# RFM50_to_IWING-MRF_2.net
KiCad netlist of a schematic drawn in EAGLE
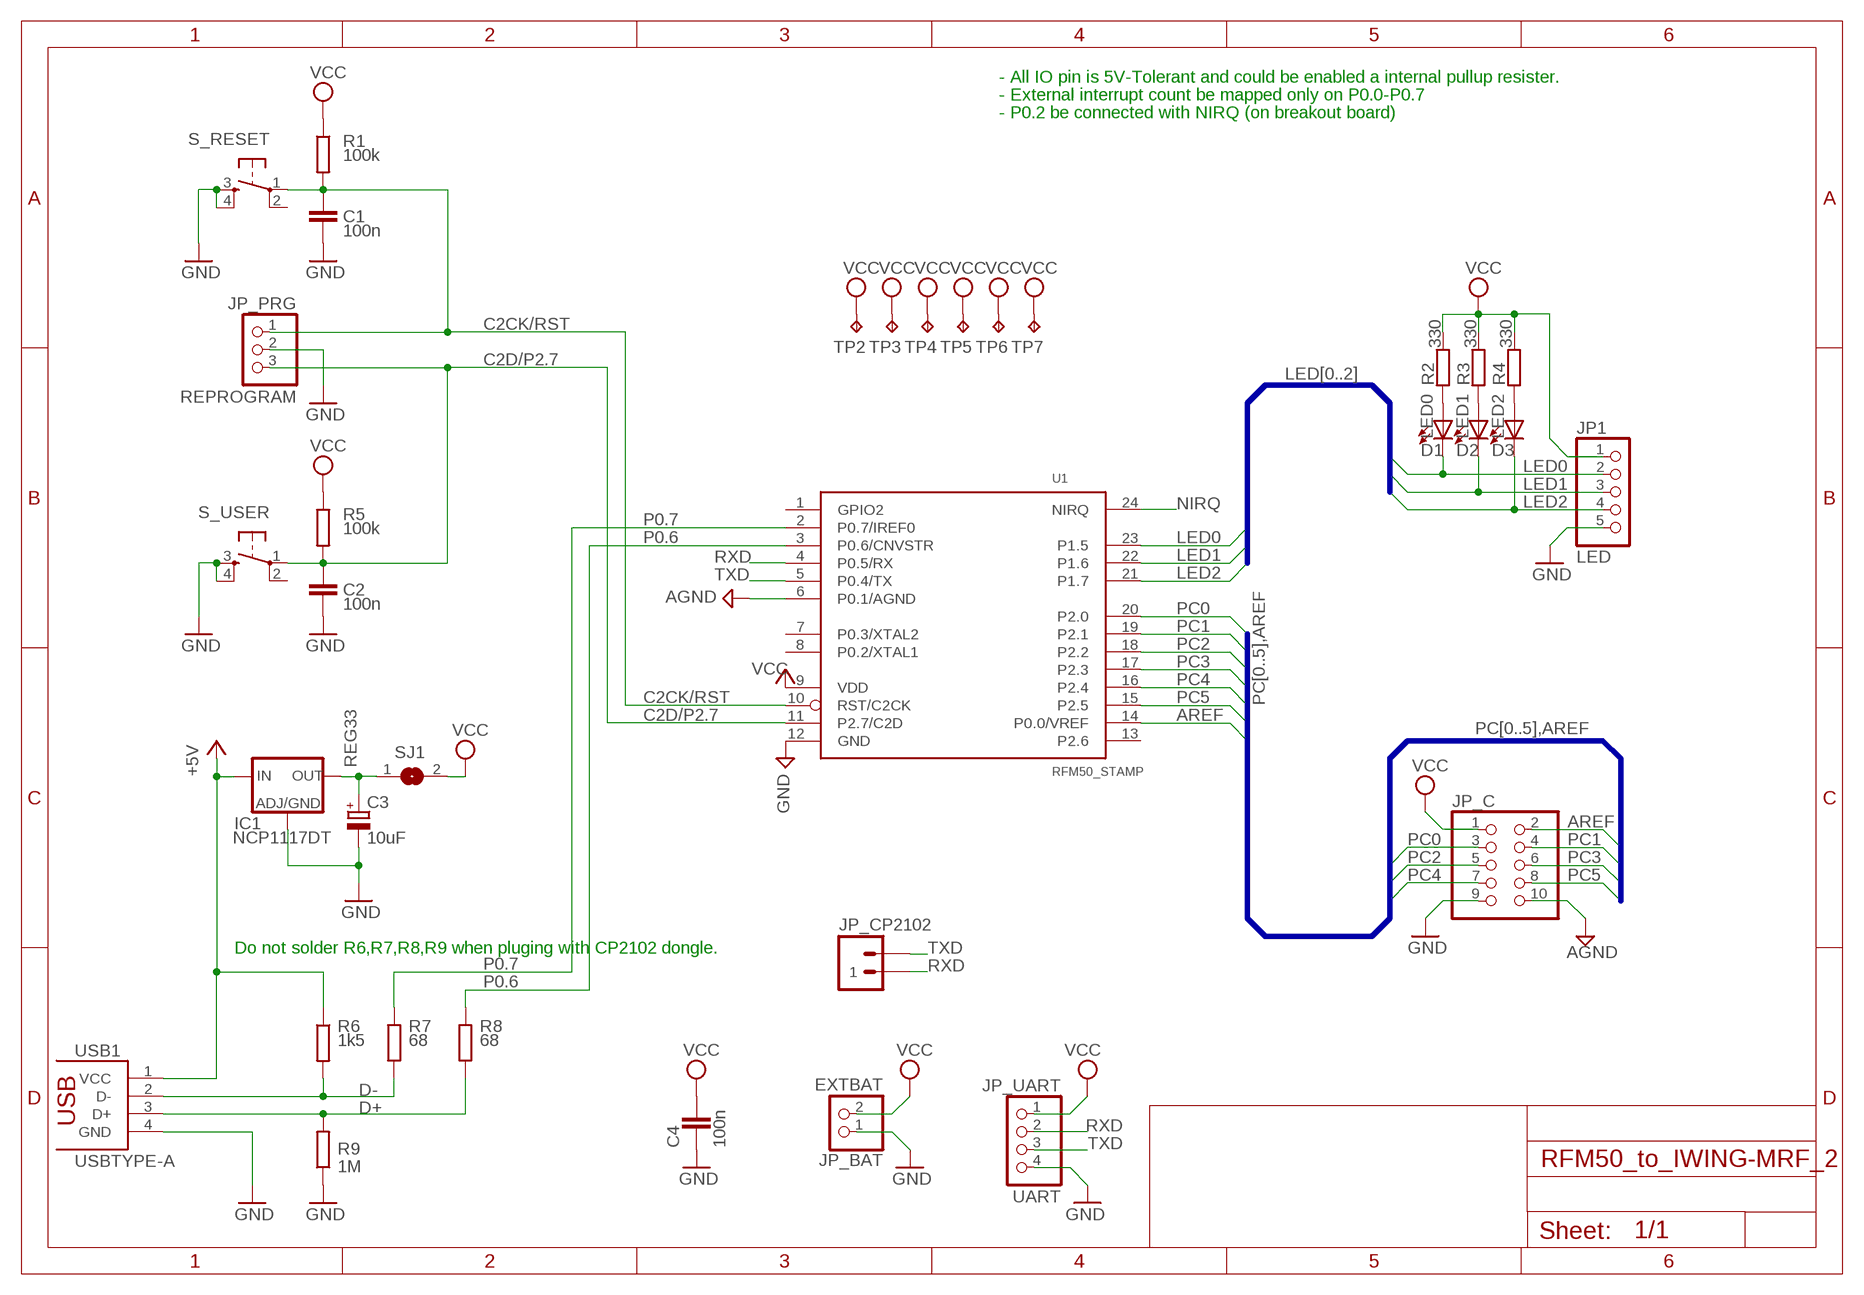
[diagram p0: schematic, sheet 1]

(export (version "E")
  (design (tool "Eeschema 10.0.6"))
  (components
    (comp (ref "C1")
      (value "100n")
      (footprint "eagle-import:C050-024X044")
      (libsource (lib "eagle-import") (part "C-EU050-024X044"))
    )
    (comp (ref "C2")
      (value "100n")
      (footprint "eagle-import:C050-024X044")
      (libsource (lib "eagle-import") (part "C-EU050-024X044"))
    )
    (comp (ref "C3")
      (value "10uF")
      (footprint "eagle-import:E2,5-6E")
      (libsource (lib "eagle-import") (part "CPOL-EUE2,5-6E"))
    )
    (comp (ref "C4")
      (value "100n")
      (footprint "eagle-import:C050-024X044")
      (libsource (lib "eagle-import") (part "C-EU050-024X044"))
    )
    (comp (ref "D1")
      (value "LED0")
      (footprint "eagle-import:LED3MM")
      (libsource (lib "eagle-import") (part "LED3MM"))
    )
    (comp (ref "D2")
      (value "LED1")
      (footprint "eagle-import:LED3MM")
      (libsource (lib "eagle-import") (part "LED3MM"))
    )
    (comp (ref "D3")
      (value "LED2")
      (footprint "eagle-import:LED3MM")
      (libsource (lib "eagle-import") (part "LED3MM"))
    )
    (comp (ref "IC1")
      (value "NCP1117DT")
      (footprint "eagle-import:DPACK")
      (libsource (lib "eagle-import") (part "NCP1117DT"))
    )
    (comp (ref "JP1")
      (value "LED")
      (footprint "eagle-import:1X05")
      (libsource (lib "eagle-import") (part "PINHD-1X5"))
    )
    (comp (ref "JP_BAT")
      (value "EXTBAT")
      (footprint "eagle-import:1X02")
      (libsource (lib "eagle-import") (part "PINHD-1X2"))
    )
    (comp (ref "JP_C")
      (value "HEADER-2X5")
      (footprint "eagle-import:2X05")
      (libsource (lib "eagle-import") (part "HEADER-2X5"))
    )
    (comp (ref "JP_CP2102")
      (value "M02PTH")
      (footprint "eagle-import:1X02")
      (libsource (lib "eagle-import") (part "M02PTH"))
    )
    (comp (ref "JP_PRG")
      (value "REPROGRAM")
      (footprint "eagle-import:1X03")
      (libsource (lib "eagle-import") (part "PINHD-1X3"))
    )
    (comp (ref "JP_UART")
      (value "UART")
      (footprint "eagle-import:1X04_ROUND")
      (libsource (lib "eagle-import") (part "HEADER-1X4ROUND"))
    )
    (comp (ref "R1")
      (value "100k")
      (footprint "eagle-import:0204_5")
      (libsource (lib "eagle-import") (part "R-EU_0204/5"))
    )
    (comp (ref "R2")
      (value "330")
      (footprint "eagle-import:0204_5")
      (libsource (lib "eagle-import") (part "R-EU_0204/5"))
    )
    (comp (ref "R3")
      (value "330")
      (footprint "eagle-import:0204_5")
      (libsource (lib "eagle-import") (part "R-EU_0204/5"))
    )
    (comp (ref "R4")
      (value "330")
      (footprint "eagle-import:0204_5")
      (libsource (lib "eagle-import") (part "R-EU_0204/5"))
    )
    (comp (ref "R5")
      (value "100k")
      (footprint "eagle-import:0204_5")
      (libsource (lib "eagle-import") (part "R-EU_0204/5"))
    )
    (comp (ref "R6")
      (value "1k5")
      (footprint "eagle-import:0204_5")
      (libsource (lib "eagle-import") (part "R-EU_0204/5"))
    )
    (comp (ref "R7")
      (value "68")
      (footprint "eagle-import:0204_5")
      (libsource (lib "eagle-import") (part "R-EU_0204/5"))
    )
    (comp (ref "R8")
      (value "68")
      (footprint "eagle-import:0204_5")
      (libsource (lib "eagle-import") (part "R-EU_0204/5"))
    )
    (comp (ref "R9")
      (value "1M")
      (footprint "eagle-import:0204_5")
      (libsource (lib "eagle-import") (part "R-EU_0204/5"))
    )
    (comp (ref "SJ1")
      (value "SOLDERJUMPERREFLOW_NOPASTE")
      (footprint "eagle-import:SOLDERJUMPER_REFLOW_NOPASTE")
      (libsource (lib "eagle-import") (part "SOLDERJUMPERREFLOW_NOPASTE"))
    )
    (comp (ref "S_RESET")
      (value "DTS-6")
      (footprint "eagle-import:DTS-6")
      (libsource (lib "eagle-import") (part "DTS-6"))
    )
    (comp (ref "S_USER")
      (value "DTS-6")
      (footprint "eagle-import:DTS-6")
      (libsource (lib "eagle-import") (part "DTS-6"))
    )
    (comp (ref "TP2")
      (value "TPPAD1-10")
      (footprint "eagle-import:P1-10_TP")
      (libsource (lib "eagle-import") (part "TPPAD1-10"))
    )
    (comp (ref "TP3")
      (value "TPPAD1-10")
      (footprint "eagle-import:P1-10_TP")
      (libsource (lib "eagle-import") (part "TPPAD1-10"))
    )
    (comp (ref "TP4")
      (value "TPPAD1-10")
      (footprint "eagle-import:P1-10_TP")
      (libsource (lib "eagle-import") (part "TPPAD1-10"))
    )
    (comp (ref "TP5")
      (value "TPPAD1-10")
      (footprint "eagle-import:P1-10_TP")
      (libsource (lib "eagle-import") (part "TPPAD1-10"))
    )
    (comp (ref "TP6")
      (value "TPPAD1-10")
      (footprint "eagle-import:P1-10_TP")
      (libsource (lib "eagle-import") (part "TPPAD1-10"))
    )
    (comp (ref "TP7")
      (value "TPPAD1-10")
      (footprint "eagle-import:P1-10_TP")
      (libsource (lib "eagle-import") (part "TPPAD1-10"))
    )
    (comp (ref "U1")
      (value "RFM50_STAMP")
      (footprint "eagle-import:RFM50_STAMP")
      (libsource (lib "eagle-import") (part "RFM50_STAMP"))
    )
    (comp (ref "USB1")
      (value "USBTYPE-A")
      (footprint "eagle-import:USBTYPE-A")
      (libsource (lib "eagle-import") (part "USBTYPE-A"))
    )
  )
  (nets
    (net (code "1") (name "+5V") (class "Default")
      (node (ref "IC1") (pin "3") (pinfunction "IN_3") (pintype "input"))
      (node (ref "R6") (pin "1") (pinfunction "1_1") (pintype "passive"))
      (node (ref "USB1") (pin "1") (pinfunction "VCC_1") (pintype "power_in"))
    )
    (net (code "2") (name "/AREF") (class "Default")
      (node (ref "JP_C") (pin "2") (pinfunction "2_2") (pintype "passive"))
      (node (ref "U1") (pin "14") (pinfunction "P0.0/VREF_14") (pintype "bidirectional"))
    )
    (net (code "3") (name "/C2CK{slash}RST") (class "Default")
      (node (ref "C1") (pin "2") (pinfunction "2_2") (pintype "passive"))
      (node (ref "JP_PRG") (pin "1") (pinfunction "1_1") (pintype "passive"))
      (node (ref "R1") (pin "2") (pinfunction "2_2") (pintype "passive"))
      (node (ref "S_RESET") (pin "1") (pinfunction "1_1") (pintype "passive"))
      (node (ref "U1") (pin "10") (pinfunction "RST/C2CK_10") (pintype "bidirectional"))
    )
    (net (code "4") (name "/C2D{slash}P2.7") (class "Default")
      (node (ref "C2") (pin "2") (pinfunction "2_2") (pintype "passive"))
      (node (ref "JP_PRG") (pin "3") (pinfunction "3_3") (pintype "passive"))
      (node (ref "R5") (pin "2") (pinfunction "2_2") (pintype "passive"))
      (node (ref "S_USER") (pin "1") (pinfunction "1_1") (pintype "passive"))
      (node (ref "U1") (pin "11") (pinfunction "P2.7/C2D_11") (pintype "bidirectional"))
    )
    (net (code "5") (name "/D+") (class "Default")
      (node (ref "R8") (pin "1") (pinfunction "1_1") (pintype "passive"))
      (node (ref "R9") (pin "2") (pinfunction "2_2") (pintype "passive"))
      (node (ref "USB1") (pin "3") (pinfunction "D+_3") (pintype "bidirectional"))
    )
    (net (code "6") (name "/D-") (class "Default")
      (node (ref "R6") (pin "2") (pinfunction "2_2") (pintype "passive"))
      (node (ref "R7") (pin "1") (pinfunction "1_1") (pintype "passive"))
      (node (ref "USB1") (pin "2") (pinfunction "D-_2") (pintype "bidirectional"))
    )
    (net (code "7") (name "/LED0") (class "Default")
      (node (ref "D1") (pin "K") (pinfunction "C_K") (pintype "passive"))
      (node (ref "JP1") (pin "2") (pinfunction "2_2") (pintype "passive"))
      (node (ref "U1") (pin "23") (pinfunction "P1.5_23") (pintype "bidirectional"))
    )
    (net (code "8") (name "/LED1") (class "Default")
      (node (ref "D2") (pin "K") (pinfunction "C_K") (pintype "passive"))
      (node (ref "JP1") (pin "3") (pinfunction "3_3") (pintype "passive"))
      (node (ref "U1") (pin "22") (pinfunction "P1.6_22") (pintype "bidirectional"))
    )
    (net (code "9") (name "/LED2") (class "Default")
      (node (ref "D3") (pin "K") (pinfunction "C_K") (pintype "passive"))
      (node (ref "JP1") (pin "4") (pinfunction "4_4") (pintype "passive"))
      (node (ref "U1") (pin "21") (pinfunction "P1.7_21") (pintype "bidirectional"))
    )
    (net (code "11") (name "/NIRQ") (class "Default")
      (node (ref "U1") (pin "24") (pinfunction "NIRQ_24") (pintype "output"))
    )
    (net (code "12") (name "/P0.6") (class "Default")
      (node (ref "R8") (pin "2") (pinfunction "2_2") (pintype "passive"))
      (node (ref "U1") (pin "3") (pinfunction "P0.6/CNVSTR_3") (pintype "bidirectional"))
    )
    (net (code "13") (name "/P0.7") (class "Default")
      (node (ref "R7") (pin "2") (pinfunction "2_2") (pintype "passive"))
      (node (ref "U1") (pin "2") (pinfunction "P0.7/IREF0_2") (pintype "bidirectional"))
    )
    (net (code "14") (name "/PC0") (class "Default")
      (node (ref "JP_C") (pin "3") (pinfunction "3_3") (pintype "passive"))
      (node (ref "U1") (pin "20") (pinfunction "P2.0_20") (pintype "bidirectional"))
    )
    (net (code "15") (name "/PC1") (class "Default")
      (node (ref "JP_C") (pin "4") (pinfunction "4_4") (pintype "passive"))
      (node (ref "U1") (pin "19") (pinfunction "P2.1_19") (pintype "bidirectional"))
    )
    (net (code "16") (name "/PC2") (class "Default")
      (node (ref "JP_C") (pin "5") (pinfunction "5_5") (pintype "passive"))
      (node (ref "U1") (pin "18") (pinfunction "P2.2_18") (pintype "bidirectional"))
    )
    (net (code "17") (name "/PC3") (class "Default")
      (node (ref "JP_C") (pin "6") (pinfunction "6_6") (pintype "passive"))
      (node (ref "U1") (pin "17") (pinfunction "P2.3_17") (pintype "bidirectional"))
    )
    (net (code "18") (name "/PC4") (class "Default")
      (node (ref "JP_C") (pin "7") (pinfunction "7_7") (pintype "passive"))
      (node (ref "U1") (pin "16") (pinfunction "P2.4_16") (pintype "bidirectional"))
    )
    (net (code "19") (name "/PC5") (class "Default")
      (node (ref "JP_C") (pin "8") (pinfunction "8_8") (pintype "passive"))
      (node (ref "U1") (pin "15") (pinfunction "P2.5_15") (pintype "bidirectional"))
    )
    (net (code "20") (name "/REG33") (class "Default")
      (node (ref "C3") (pin "+") (pinfunction "+_+") (pintype "passive"))
      (node (ref "IC1") (pin "4") (pinfunction "OUT_4") (pintype "passive"))
      (node (ref "SJ1") (pin "1") (pinfunction "1_1") (pintype "passive"))
    )
    (net (code "21") (name "/RXD") (class "Default")
      (node (ref "JP_CP2102") (pin "1") (pinfunction "1_1") (pintype "passive"))
      (node (ref "JP_UART") (pin "2") (pinfunction "2_2") (pintype "passive"))
      (node (ref "U1") (pin "4") (pinfunction "P0.5/RX_4") (pintype "bidirectional"))
    )
    (net (code "22") (name "/TXD") (class "Default")
      (node (ref "JP_CP2102") (pin "2") (pinfunction "2_2") (pintype "passive"))
      (node (ref "JP_UART") (pin "3") (pinfunction "3_3") (pintype "passive"))
      (node (ref "U1") (pin "5") (pinfunction "P0.4/TX_5") (pintype "bidirectional"))
    )
    (net (code "24") (name "AGND") (class "Default")
      (node (ref "JP_C") (pin "10") (pinfunction "10_10") (pintype "passive"))
      (node (ref "U1") (pin "6") (pinfunction "P0.1/AGND_6") (pintype "bidirectional"))
    )
    (net (code "25") (name "GND") (class "Default")
      (node (ref "C1") (pin "1") (pinfunction "1_1") (pintype "passive"))
      (node (ref "C2") (pin "1") (pinfunction "1_1") (pintype "passive"))
      (node (ref "C3") (pin "-") (pinfunction "-_-") (pintype "passive"))
      (node (ref "C4") (pin "1") (pinfunction "1_1") (pintype "passive"))
      (node (ref "IC1") (pin "1") (pinfunction "ADJ_1") (pintype "input"))
      (node (ref "JP1") (pin "5") (pinfunction "5_5") (pintype "passive"))
      (node (ref "JP_BAT") (pin "1") (pinfunction "1_1") (pintype "passive"))
      (node (ref "JP_C") (pin "9") (pinfunction "9_9") (pintype "passive"))
      (node (ref "JP_PRG") (pin "2") (pinfunction "2_2") (pintype "passive"))
      (node (ref "JP_UART") (pin "4") (pinfunction "4_4") (pintype "passive"))
      (node (ref "R9") (pin "1") (pinfunction "1_1") (pintype "passive"))
      (node (ref "S_RESET") (pin "3") (pinfunction "3_3") (pintype "passive"))
      (node (ref "S_RESET") (pin "4") (pinfunction "4_4") (pintype "passive"))
      (node (ref "S_USER") (pin "3") (pinfunction "3_3") (pintype "passive"))
      (node (ref "S_USER") (pin "4") (pinfunction "4_4") (pintype "passive"))
      (node (ref "U1") (pin "12") (pinfunction "GND_12") (pintype "bidirectional"))
      (node (ref "USB1") (pin "4") (pinfunction "GND_4") (pintype "power_in"))
    )
    (net (code "26") (name "Net-(D1-PadA)") (class "Default")
      (node (ref "D1") (pin "A") (pinfunction "A_A") (pintype "passive"))
      (node (ref "R2") (pin "2") (pinfunction "2_2") (pintype "passive"))
    )
    (net (code "27") (name "Net-(D2-PadA)") (class "Default")
      (node (ref "D2") (pin "A") (pinfunction "A_A") (pintype "passive"))
      (node (ref "R3") (pin "2") (pinfunction "2_2") (pintype "passive"))
    )
    (net (code "28") (name "Net-(D3-PadA)") (class "Default")
      (node (ref "D3") (pin "A") (pinfunction "A_A") (pintype "passive"))
      (node (ref "R4") (pin "2") (pinfunction "2_2") (pintype "passive"))
    )
    (net (code "29") (name "VCC") (class "Default")
      (node (ref "C4") (pin "2") (pinfunction "2_2") (pintype "passive"))
      (node (ref "JP1") (pin "1") (pinfunction "1_1") (pintype "passive"))
      (node (ref "JP_BAT") (pin "2") (pinfunction "2_2") (pintype "passive"))
      (node (ref "JP_C") (pin "1") (pinfunction "1_1") (pintype "passive"))
      (node (ref "JP_UART") (pin "1") (pinfunction "1_1") (pintype "passive"))
      (node (ref "R1") (pin "1") (pinfunction "1_1") (pintype "passive"))
      (node (ref "R2") (pin "1") (pinfunction "1_1") (pintype "passive"))
      (node (ref "R3") (pin "1") (pinfunction "1_1") (pintype "passive"))
      (node (ref "R4") (pin "1") (pinfunction "1_1") (pintype "passive"))
      (node (ref "R5") (pin "1") (pinfunction "1_1") (pintype "passive"))
      (node (ref "SJ1") (pin "2") (pinfunction "2_2") (pintype "passive"))
      (node (ref "TP2") (pin "TP") (pinfunction "TP_TP") (pintype "input"))
      (node (ref "TP3") (pin "TP") (pinfunction "TP_TP") (pintype "input"))
      (node (ref "TP4") (pin "TP") (pinfunction "TP_TP") (pintype "input"))
      (node (ref "TP5") (pin "TP") (pinfunction "TP_TP") (pintype "input"))
      (node (ref "TP6") (pin "TP") (pinfunction "TP_TP") (pintype "input"))
      (node (ref "TP7") (pin "TP") (pinfunction "TP_TP") (pintype "input"))
      (node (ref "U1") (pin "9") (pinfunction "VDD_9") (pintype "power_in"))
    )
    (net (code "30") (name "unconnected-(S_RESET-Pad2)") (class "Default")
      (node (ref "S_RESET") (pin "2") (pinfunction "2_2") (pintype "passive"))
    )
    (net (code "31") (name "unconnected-(S_USER-Pad2)") (class "Default")
      (node (ref "S_USER") (pin "2") (pinfunction "2_2") (pintype "passive"))
    )
    (net (code "32") (name "unconnected-(U1-GPIO2-Pad1)") (class "Default")
      (node (ref "U1") (pin "1") (pinfunction "GPIO2_1") (pintype "bidirectional"))
    )
    (net (code "33") (name "unconnected-(U1-P0.2{slash}XTAL1-Pad8)") (class "Default")
      (node (ref "U1") (pin "8") (pinfunction "P0.2/XTAL1_8") (pintype "bidirectional"))
    )
    (net (code "34") (name "unconnected-(U1-P0.3{slash}XTAL2-Pad7)") (class "Default")
      (node (ref "U1") (pin "7") (pinfunction "P0.3/XTAL2_7") (pintype "bidirectional"))
    )
    (net (code "35") (name "unconnected-(U1-P2.6-Pad13)") (class "Default")
      (node (ref "U1") (pin "13") (pinfunction "P2.6_13") (pintype "bidirectional"))
    )
  )
)
